# 5and12v.net
KiCad netlist of a schematic drawn in Altium Designer
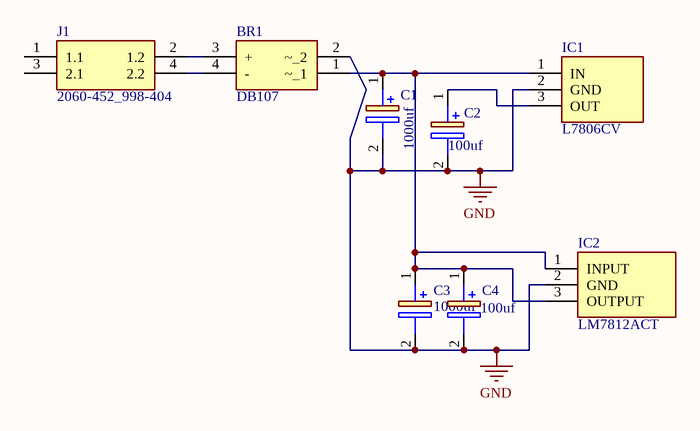
[diagram p0: 5and12v.SchDoc]

(export (version "E")
  (design (tool "Eeschema 10.0.6"))
  (components
    (comp (ref "BR1")
      (value "DB107")
      (footprint "SamacSys:DIP825W50P510L830H340Q4N")
      (description "Bridge Rectifier")
      (fields (field (name "MOUSER PART NUMBER") "583-DB107"))
      (libsource (lib "*") (part "DB107"))
    )
    (comp (ref "C1")
      (value "1000uf")
      (footprint "SamacSys:CAPPRD550W60D1050H2150")
      (description "Capacitor Polarised")
      (fields (field (name "MANUFACTURER_PART_NUMBER") "108CKE025M"))
      (libsource (lib "*") (part "108CKE025M"))
    )
    (comp (ref "C2")
      (value "100uf")
      (footprint "SamacSys:CAPPRD500W65D1000H3200")
      (description "Capacitor Polarised")
      (fields
        (field (name "MANUFACTURER_PART_NUMBER") "EEU-FC2A101L")
        (field (name "MOUSER PART NUMBER") "667-EEU-FC2A101L")
      )
      (libsource (lib "*") (part "EEU-FC2A101L"))
    )
    (comp (ref "C3")
      (value "1000uf")
      (footprint "SamacSys:CAPPRD550W60D1050H2150")
      (description "Capacitor Polarised")
      (fields (field (name "MANUFACTURER_PART_NUMBER") "108CKE025M"))
      (libsource (lib "SamacSys") (part "108CKE025M"))
    )
    (comp (ref "C4")
      (value "100uf")
      (footprint "SamacSys:CAPPRD500W65D1000H3200")
      (description "Capacitor Polarised")
      (fields
        (field (name "MANUFACTURER_PART_NUMBER") "EEU-FC2A101L")
        (field (name "MOUSER PART NUMBER") "667-EEU-FC2A101L")
      )
      (libsource (lib "*") (part "EEU-FC2A101L"))
    )
    (comp (ref "IC1")
      (value "L7806CV")
      (footprint "SamacSys:TO270P460X1020X2008-3P")
      (description "Integrated Circuit")
      (fields (field (name "MOUSER PART NUMBER") "511-L7806CV"))
      (libsource (lib "*") (part "L7806CV"))
    )
    (comp (ref "IC2")
      (value "LM7812ACT")
      (footprint "SamacSys:TO254P470X1016X2019-3P")
      (description "Integrated Circuit")
      (fields (field (name "MOUSER PART NUMBER") "512-LM7812ACT"))
      (libsource (lib "SamacSys") (part "LM7812ACT"))
    )
    (comp (ref "J1")
      (value "2060-452_998-404")
      (footprint "SamacSys:2060452998404")
      (description "Connector")
      (fields (field (name "MANUFACTURER_PART_NUMBER") "2060-452/998-404"))
      (libsource (lib "*") (part "2060-452_998-404"))
    )
  )
  (nets
    (net (code "1") (name "GND") (class "Default")
      (node (ref "BR1") (pin "2") (pinfunction "~_2_2") (pintype "passive"))
      (node (ref "C1") (pin "2") (pinfunction "-_2") (pintype "passive"))
      (node (ref "C2") (pin "2") (pinfunction "-_2") (pintype "passive"))
      (node (ref "C3") (pin "2") (pinfunction "-_2") (pintype "passive"))
      (node (ref "C4") (pin "2") (pinfunction "-_2") (pintype "passive"))
      (node (ref "IC1") (pin "2") (pinfunction "GND_2") (pintype "power_in"))
      (node (ref "IC2") (pin "2") (pinfunction "GND_2") (pintype "passive"))
    )
    (net (code "2") (name "Net-(BR1-+)") (class "Default")
      (node (ref "BR1") (pin "3") (pinfunction "+_3") (pintype "passive"))
      (node (ref "J1") (pin "2") (pinfunction "1.2_2") (pintype "passive"))
    )
    (net (code "3") (name "Net-(BR1--)") (class "Default")
      (node (ref "BR1") (pin "4") (pinfunction "-_4") (pintype "passive"))
      (node (ref "J1") (pin "4") (pinfunction "2.2_4") (pintype "passive"))
    )
    (net (code "4") (name "Net-(BR1-~_1)") (class "Default")
      (node (ref "BR1") (pin "1") (pinfunction "~_1_1") (pintype "passive"))
      (node (ref "C1") (pin "1") (pinfunction "+_1") (pintype "passive"))
      (node (ref "C3") (pin "1") (pinfunction "+_1") (pintype "passive"))
      (node (ref "C4") (pin "1") (pinfunction "+_1") (pintype "passive"))
      (node (ref "IC1") (pin "1") (pinfunction "IN_1") (pintype "power_in"))
      (node (ref "IC2") (pin "1") (pinfunction "INPUT_1") (pintype "passive"))
      (node (ref "IC2") (pin "3") (pinfunction "OUTPUT_3") (pintype "passive"))
    )
    (net (code "5") (name "Net-(C2-+)") (class "Default")
      (node (ref "C2") (pin "1") (pinfunction "+_1") (pintype "passive"))
      (node (ref "IC1") (pin "3") (pinfunction "OUT_3") (pintype "power_in"))
    )
    (net (code "6") (name "unconnected-(J1-1.1-Pad1)") (class "Default")
      (node (ref "J1") (pin "1") (pinfunction "1.1_1") (pintype "passive"))
    )
    (net (code "7") (name "unconnected-(J1-2.1-Pad3)") (class "Default")
      (node (ref "J1") (pin "3") (pinfunction "2.1_3") (pintype "passive"))
    )
  )
)
